# pn532.net
KiCad netlist of a schematic drawn in Altium Designer
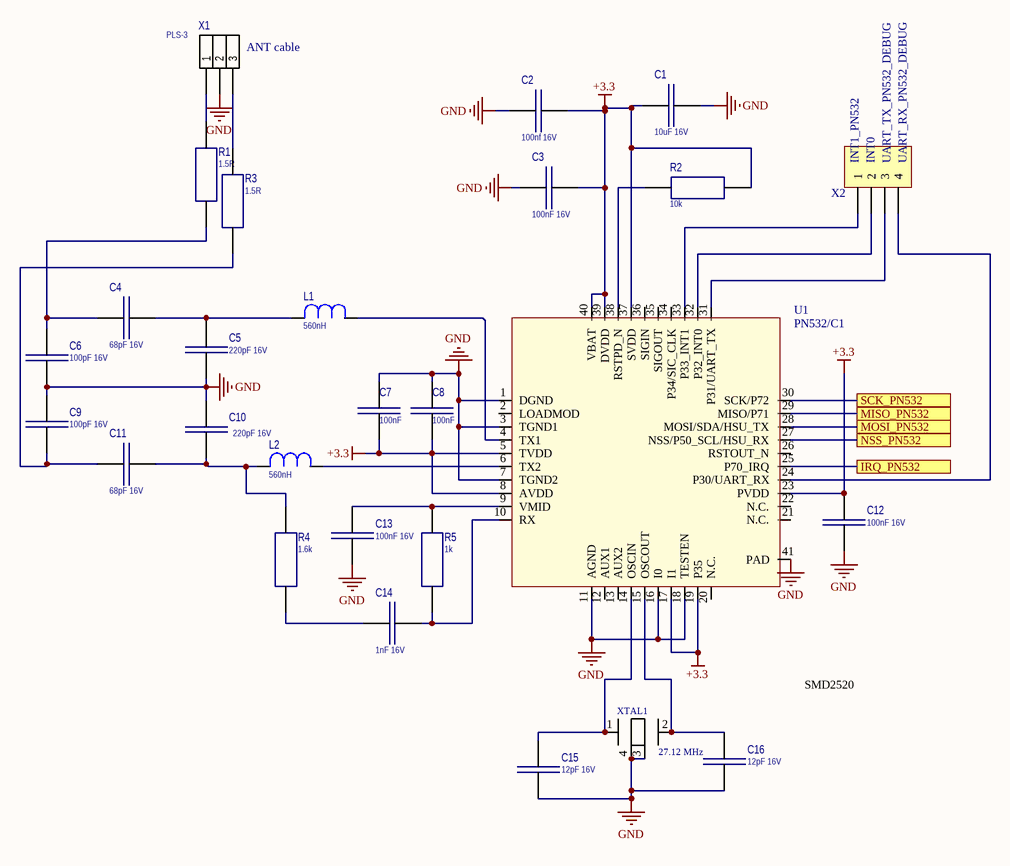
[diagram p0: pn532.SchDoc]

(export (version "E")
  (design (tool "Eeschema 10.0.6"))
  (components
    (comp (ref "C1")
      (value "10uF 16V")
      (footprint "C_0805")
      (description "Capacitor")
      (libsource (lib "AX_Altium_v2.3") (part "C0805"))
    )
    (comp (ref "C2")
      (value "100nf 16V")
      (footprint "C_0805")
      (description "Capacitor")
      (libsource (lib "AX_Altium_v2.3") (part "C0805"))
    )
    (comp (ref "C3")
      (value "100nF 16V")
      (footprint "C_0805")
      (description "Capacitor")
      (libsource (lib "AX_Altium_v2.3") (part "C0805"))
    )
    (comp (ref "C4")
      (value "68pF 16V")
      (footprint "C_0805")
      (description "Capacitor")
      (libsource (lib "AX_Altium_v2.3") (part "C0805"))
    )
    (comp (ref "C5")
      (value "220pF 16V")
      (footprint "C_0805")
      (description "Capacitor")
      (libsource (lib "AX_Altium_v2.3") (part "C0805"))
    )
    (comp (ref "C6")
      (value "100pF 16V")
      (footprint "C_0805")
      (description "Capacitor")
      (libsource (lib "AX_Altium_v2.3") (part "C0805"))
    )
    (comp (ref "C7")
      (value "100nF")
      (footprint "C_0805")
      (description "Capacitor")
      (libsource (lib "AX_Altium_v2.3") (part "C0805"))
    )
    (comp (ref "C8")
      (value "100nF")
      (footprint "C_0805")
      (description "Capacitor")
      (libsource (lib "AX_Altium_v2.3") (part "C0805"))
    )
    (comp (ref "C9")
      (value "100pF 16V")
      (footprint "C_0805")
      (description "Capacitor")
      (libsource (lib "AX_Altium_v2.3") (part "C0805"))
    )
    (comp (ref "C10")
      (value "220pF 16V")
      (footprint "C_0805")
      (description "Capacitor")
      (libsource (lib "AX_Altium_v2.3") (part "C0805"))
    )
    (comp (ref "C11")
      (value "68pF 16V")
      (footprint "C_0805")
      (description "Capacitor")
      (libsource (lib "AX_Altium_v2.3") (part "C0805"))
    )
    (comp (ref "C12")
      (value "100nF 16V")
      (footprint "C_0805")
      (description "Capacitor")
      (libsource (lib "AX_Altium_v2.3") (part "C0805"))
    )
    (comp (ref "C13")
      (value "100nF 16V")
      (footprint "C_0805")
      (description "Capacitor")
      (libsource (lib "AX_Altium_v2.3") (part "C0805"))
    )
    (comp (ref "C14")
      (value "1nF 16V")
      (footprint "C_0805")
      (description "Capacitor")
      (libsource (lib "AX_Altium_v2.3") (part "C0805"))
    )
    (comp (ref "C15")
      (value "12pF 16V")
      (footprint "C_0805")
      (description "Capacitor")
      (libsource (lib "AX_Altium_v2.3") (part "C0805"))
    )
    (comp (ref "C16")
      (value "12pF 16V")
      (footprint "C_0805")
      (description "Capacitor")
      (libsource (lib "AX_Altium_v2.3") (part "C0805"))
    )
    (comp (ref "L1")
      (value "560nH")
      (footprint "L_0805")
      (description "MLF2012DR56K")
      (libsource (lib "AX_Altium_v2.3") (part "L0805"))
    )
    (comp (ref "L2")
      (value "560nH")
      (footprint "L_0805")
      (description "MLF2012DR56K")
      (libsource (lib "AX_Altium_v2.3") (part "L0805"))
    )
    (comp (ref "R1")
      (value "1.5R")
      (footprint "R_0805")
      (description "Resistor")
      (libsource (lib "AX_Altium_v2.3") (part "R0805"))
    )
    (comp (ref "R2")
      (value "10k")
      (footprint "R_0805")
      (description "Resistor")
      (libsource (lib "AX_Altium_v2.3") (part "R0805"))
    )
    (comp (ref "R3")
      (value "1.5R")
      (footprint "R_0805")
      (description "Resistor")
      (libsource (lib "AX_Altium_v2.3") (part "R0805"))
    )
    (comp (ref "R4")
      (value "1.6k")
      (footprint "R_0805")
      (description "Resistor")
      (libsource (lib "AX_Altium_v2.3") (part "R0805"))
    )
    (comp (ref "R5")
      (value "1k")
      (footprint "R_0805")
      (description "Resistor")
      (libsource (lib "AX_Altium_v2.3") (part "R0805"))
    )
    (comp (ref "U1")
      (value "PN532/C1")
      (footprint "NXP-HVQFN-40_L")
      (libsource (lib "pn532") (part "PN532/C1"))
    )
    (comp (ref "X1")
      (value "PLS-3")
      (footprint "PLS-3-3D")
      (description "Header, 3-Pin")
      (fields (field (name "PUBLISHER") "Altium Limited"))
      (libsource (lib "ConnectorButtonSocetDisplay") (part "PLS-3"))
    )
    (comp (ref "X2")
      (value "PLS-4")
      (footprint "PLS-4-3D")
      (description "Header, 4-Pin")
      (fields (field (name "PUBLISHER") "Altium Limited"))
      (libsource (lib "ConnectorButtonSocetDisplay") (part "PLS-4"))
    )
    (comp (ref "XTAL1")
      (value "27.12 MHz")
      (footprint "NX2520SA")
      (description "Quartz")
      (libsource (lib "Quartz") (part "NX2520SA"))
    )
  )
  (nets
    (net (code "1") (name "+3.3") (class "Default")
      (node (ref "C1") (pin "2") (pinfunction "2_2") (pintype "passive"))
      (node (ref "C12") (pin "2") (pinfunction "2_2") (pintype "passive"))
      (node (ref "C2") (pin "1") (pinfunction "1_1") (pintype "passive"))
      (node (ref "C3") (pin "1") (pinfunction "1_1") (pintype "passive"))
      (node (ref "C7") (pin "1") (pinfunction "1_1") (pintype "passive"))
      (node (ref "C8") (pin "1") (pinfunction "1_1") (pintype "passive"))
      (node (ref "R2") (pin "1") (pinfunction "1_1") (pintype "passive"))
      (node (ref "U1") (pin "17") (pinfunction "I1_17") (pintype "passive"))
      (node (ref "U1") (pin "19") (pinfunction "P35_19") (pintype "passive"))
      (node (ref "U1") (pin "23") (pinfunction "PVDD_23") (pintype "passive"))
      (node (ref "U1") (pin "37") (pinfunction "SVDD_37") (pintype "passive"))
      (node (ref "U1") (pin "39") (pinfunction "DVDD_39") (pintype "passive"))
      (node (ref "U1") (pin "40") (pinfunction "VBAT_40") (pintype "passive"))
      (node (ref "U1") (pin "5") (pinfunction "TVDD_5") (pintype "passive"))
      (node (ref "U1") (pin "8") (pinfunction "AVDD_8") (pintype "passive"))
    )
    (net (code "2") (name "/IRQ_PN532") (class "Default")
      (node (ref "U1") (pin "25") (pinfunction "P70_IRQ_25") (pintype "passive"))
    )
    (net (code "3") (name "/MISO_PN532") (class "Default")
      (node (ref "U1") (pin "29") (pinfunction "MISO/P71_29") (pintype "passive"))
    )
    (net (code "4") (name "/MOSI_PN532") (class "Default")
      (node (ref "U1") (pin "28") (pinfunction "MOSI/SDA/HSU_TX_28") (pintype "passive"))
    )
    (net (code "5") (name "/NSS_PN532") (class "Default")
      (node (ref "U1") (pin "27") (pinfunction "NSS/P50_SCL/HSU_RX_27") (pintype "passive"))
    )
    (net (code "6") (name "/SCK_PN532") (class "Default")
      (node (ref "U1") (pin "30") (pinfunction "SCK/P72_30") (pintype "passive"))
    )
    (net (code "7") (name "GND") (class "Default")
      (node (ref "C1") (pin "1") (pinfunction "1_1") (pintype "passive"))
      (node (ref "C10") (pin "2") (pinfunction "2_2") (pintype "passive"))
      (node (ref "C12") (pin "1") (pinfunction "1_1") (pintype "passive"))
      (node (ref "C13") (pin "1") (pinfunction "1_1") (pintype "passive"))
      (node (ref "C15") (pin "1") (pinfunction "1_1") (pintype "passive"))
      (node (ref "C16") (pin "1") (pinfunction "1_1") (pintype "passive"))
      (node (ref "C2") (pin "2") (pinfunction "2_2") (pintype "passive"))
      (node (ref "C3") (pin "2") (pinfunction "2_2") (pintype "passive"))
      (node (ref "C5") (pin "1") (pinfunction "1_1") (pintype "passive"))
      (node (ref "C6") (pin "1") (pinfunction "1_1") (pintype "passive"))
      (node (ref "C7") (pin "2") (pinfunction "2_2") (pintype "passive"))
      (node (ref "C8") (pin "2") (pinfunction "2_2") (pintype "passive"))
      (node (ref "C9") (pin "2") (pinfunction "2_2") (pintype "passive"))
      (node (ref "U1") (pin "1") (pinfunction "DGND_1") (pintype "passive"))
      (node (ref "U1") (pin "11") (pinfunction "AGND_11") (pintype "passive"))
      (node (ref "U1") (pin "16") (pinfunction "I0_16") (pintype "passive"))
      (node (ref "U1") (pin "18") (pinfunction "TESTEN_18") (pintype "passive"))
      (node (ref "U1") (pin "3") (pinfunction "TGND1_3") (pintype "passive"))
      (node (ref "U1") (pin "41") (pinfunction "PAD_41") (pintype "passive"))
      (node (ref "U1") (pin "7") (pinfunction "TGND2_7") (pintype "passive"))
      (node (ref "X1") (pin "2") (pinfunction "2_2") (pintype "passive"))
      (node (ref "XTAL1") (pin "3") (pintype "passive"))
      (node (ref "XTAL1") (pin "4") (pintype "passive"))
    )
    (net (code "8") (name "Net-(C4-Pad1)") (class "Default")
      (node (ref "C4") (pin "1") (pinfunction "1_1") (pintype "passive"))
      (node (ref "C5") (pin "2") (pinfunction "2_2") (pintype "passive"))
      (node (ref "L1") (pin "1") (pintype "passive"))
    )
    (net (code "9") (name "Net-(C4-Pad2)") (class "Default")
      (node (ref "C4") (pin "2") (pinfunction "2_2") (pintype "passive"))
      (node (ref "C6") (pin "2") (pinfunction "2_2") (pintype "passive"))
      (node (ref "R1") (pin "1") (pinfunction "1_1") (pintype "passive"))
    )
    (net (code "10") (name "Net-(C10-Pad1)") (class "Default")
      (node (ref "C10") (pin "1") (pinfunction "1_1") (pintype "passive"))
      (node (ref "C11") (pin "1") (pinfunction "1_1") (pintype "passive"))
      (node (ref "L2") (pin "1") (pintype "passive"))
      (node (ref "R4") (pin "2") (pinfunction "2_2") (pintype "passive"))
    )
    (net (code "11") (name "Net-(C11-Pad2)") (class "Default")
      (node (ref "C11") (pin "2") (pinfunction "2_2") (pintype "passive"))
      (node (ref "C9") (pin "1") (pinfunction "1_1") (pintype "passive"))
      (node (ref "R3") (pin "1") (pinfunction "1_1") (pintype "passive"))
    )
    (net (code "12") (name "Net-(C14-Pad2)") (class "Default")
      (node (ref "C14") (pin "2") (pinfunction "2_2") (pintype "passive"))
      (node (ref "R4") (pin "1") (pinfunction "1_1") (pintype "passive"))
    )
    (net (code "13") (name "Net-(R1-Pad2)") (class "Default")
      (node (ref "R1") (pin "2") (pinfunction "2_2") (pintype "passive"))
      (node (ref "X1") (pin "1") (pinfunction "1_1") (pintype "passive"))
    )
    (net (code "14") (name "Net-(R3-Pad2)") (class "Default")
      (node (ref "R3") (pin "2") (pinfunction "2_2") (pintype "passive"))
      (node (ref "X1") (pin "3") (pinfunction "3_3") (pintype "passive"))
    )
    (net (code "15") (name "Net-(U1-OSCIN)") (class "Default")
      (node (ref "C15") (pin "2") (pinfunction "2_2") (pintype "passive"))
      (node (ref "U1") (pin "14") (pinfunction "OSCIN_14") (pintype "passive"))
      (node (ref "XTAL1") (pin "1") (pintype "passive"))
    )
    (net (code "16") (name "Net-(U1-OSCOUT)") (class "Default")
      (node (ref "C16") (pin "2") (pinfunction "2_2") (pintype "passive"))
      (node (ref "U1") (pin "15") (pinfunction "OSCOUT_15") (pintype "passive"))
      (node (ref "XTAL1") (pin "2") (pintype "passive"))
    )
    (net (code "17") (name "Net-(U1-P30{slash}UART_RX)") (class "Default")
      (node (ref "U1") (pin "24") (pinfunction "P30/UART_RX_24") (pintype "passive"))
      (node (ref "X2") (pin "4") (pinfunction "4_4") (pintype "passive"))
    )
    (net (code "18") (name "Net-(U1-P31{slash}UART_TX)") (class "Default")
      (node (ref "U1") (pin "31") (pinfunction "P31/UART_TX_31") (pintype "passive"))
      (node (ref "X2") (pin "3") (pinfunction "3_3") (pintype "passive"))
    )
    (net (code "19") (name "Net-(U1-P32_INT0)") (class "Default")
      (node (ref "U1") (pin "32") (pinfunction "P32_INT0_32") (pintype "passive"))
      (node (ref "X2") (pin "2") (pinfunction "2_2") (pintype "passive"))
    )
    (net (code "20") (name "Net-(U1-P33_INT1)") (class "Default")
      (node (ref "U1") (pin "33") (pinfunction "P33_INT1_33") (pintype "passive"))
      (node (ref "X2") (pin "1") (pinfunction "1_1") (pintype "passive"))
    )
    (net (code "21") (name "Net-(U1-RSTPD_N)") (class "Default")
      (node (ref "R2") (pin "2") (pinfunction "2_2") (pintype "passive"))
      (node (ref "U1") (pin "38") (pinfunction "RSTPD_N_38") (pintype "passive"))
    )
    (net (code "22") (name "Net-(U1-RX)") (class "Default")
      (node (ref "C14") (pin "1") (pinfunction "1_1") (pintype "passive"))
      (node (ref "R5") (pin "1") (pinfunction "1_1") (pintype "passive"))
      (node (ref "U1") (pin "10") (pinfunction "RX_10") (pintype "passive"))
    )
    (net (code "23") (name "Net-(U1-TX1)") (class "Default")
      (node (ref "L1") (pin "2") (pintype "passive"))
      (node (ref "U1") (pin "4") (pinfunction "TX1_4") (pintype "passive"))
    )
    (net (code "24") (name "Net-(U1-TX2)") (class "Default")
      (node (ref "L2") (pin "2") (pintype "passive"))
      (node (ref "U1") (pin "6") (pinfunction "TX2_6") (pintype "passive"))
    )
    (net (code "25") (name "Net-(U1-VMID)") (class "Default")
      (node (ref "C13") (pin "2") (pinfunction "2_2") (pintype "passive"))
      (node (ref "R5") (pin "2") (pinfunction "2_2") (pintype "passive"))
      (node (ref "U1") (pin "9") (pinfunction "VMID_9") (pintype "passive"))
    )
    (net (code "26") (name "unconnected-(U1-AUX1-Pad12)") (class "Default")
      (node (ref "U1") (pin "12") (pinfunction "AUX1_12") (pintype "passive"))
    )
    (net (code "27") (name "unconnected-(U1-AUX2-Pad13)") (class "Default")
      (node (ref "U1") (pin "13") (pinfunction "AUX2_13") (pintype "passive"))
    )
    (net (code "28") (name "unconnected-(U1-LOADMOD-Pad2)") (class "Default")
      (node (ref "U1") (pin "2") (pinfunction "LOADMOD_2") (pintype "passive"))
    )
    (net (code "29") (name "unconnected-(U1-N.C.-Pad20)") (class "Default")
      (node (ref "U1") (pin "20") (pinfunction "N.C._20") (pintype "passive"))
    )
    (net (code "30") (name "unconnected-(U1-N.C.-Pad21)") (class "Default")
      (node (ref "U1") (pin "21") (pinfunction "N.C._21") (pintype "passive"))
    )
    (net (code "31") (name "unconnected-(U1-N.C.-Pad22)") (class "Default")
      (node (ref "U1") (pin "22") (pinfunction "N.C._22") (pintype "passive"))
    )
    (net (code "32") (name "unconnected-(U1-P34{slash}SIC_CLK-Pad34)") (class "Default")
      (node (ref "U1") (pin "34") (pinfunction "P34/SIC_CLK_34") (pintype "passive"))
    )
    (net (code "33") (name "unconnected-(U1-RSTOUT_N-Pad26)") (class "Default")
      (node (ref "U1") (pin "26") (pinfunction "RSTOUT_N_26") (pintype "passive"))
    )
    (net (code "34") (name "unconnected-(U1-SIGIN-Pad36)") (class "Default")
      (node (ref "U1") (pin "36") (pinfunction "SIGIN_36") (pintype "passive"))
    )
    (net (code "35") (name "unconnected-(U1-SIGOUT-Pad35)") (class "Default")
      (node (ref "U1") (pin "35") (pinfunction "SIGOUT_35") (pintype "passive"))
    )
  )
)
